# LED.net
KiCad netlist of a schematic drawn in Altium Designer
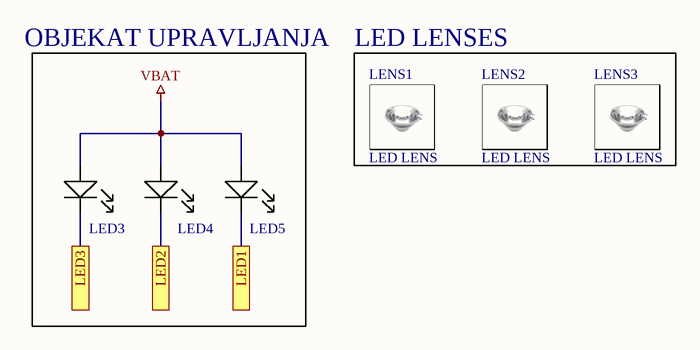
[diagram p0: LED.SchDoc]

(export (version "E")
  (design (tool "Eeschema 10.0.6"))
  (components
    (comp (ref "LED3")
      (value "JB2835BWT-N-U65EA0000-N000P001")
      (footprint "LED_1411")
      (description "LED Lighting J White, Cool 6500K 3-Step MacAdam Ellipse 2.7V 55mA 120° 1411 (3528 Metric)")
      (libsource (lib "Library-AutomatskoOsvetljenje") (part "LED COOL WHITE"))
    )
    (comp (ref "LED4")
      (value "JB2835BWT-N-U65EA0000-N000P001")
      (footprint "LED_1411")
      (description "LED Lighting J White, Cool 6500K 3-Step MacAdam Ellipse 2.7V 55mA 120° 1411 (3528 Metric)")
      (libsource (lib "Library-AutomatskoOsvetljenje") (part "LED COOL WHITE"))
    )
    (comp (ref "LED5")
      (value "JB2835BWT-N-U65EA0000-N000P001")
      (footprint "LED_1411")
      (description "LED Lighting J White, Cool 6500K 3-Step MacAdam Ellipse 2.7V 55mA 120° 1411 (3528 Metric)")
      (libsource (lib "Library-AutomatskoOsvetljenje") (part "LED COOL WHITE"))
    )
    (comp (ref "LENS1")
      (value "LED LENS")
      (description "LENS CLR 15-33DEG MEDIUM SNAP-IN")
      (fields (field (name "MPN") "10003/15"))
      (libsource (lib "Library-AutomatskoOsvetljenje") (part "LED LENS"))
    )
    (comp (ref "LENS2")
      (value "LED LENS")
      (description "LENS CLR 15-33DEG MEDIUM SNAP-IN")
      (fields (field (name "MPN") "10003/15"))
      (libsource (lib "Library-AutomatskoOsvetljenje") (part "LED LENS"))
    )
    (comp (ref "LENS3")
      (value "LED LENS")
      (description "LENS CLR 15-33DEG MEDIUM SNAP-IN")
      (fields (field (name "MPN") "10003/15"))
      (libsource (lib "Library-AutomatskoOsvetljenje") (part "LED LENS"))
    )
  )
  (nets
    (net (code "1") (name "/LED1") (class "Default")
      (node (ref "LED5") (pin "2") (pinfunction "Cathode_2") (pintype "passive"))
    )
    (net (code "2") (name "/LED2") (class "Default")
      (node (ref "LED4") (pin "2") (pinfunction "Cathode_2") (pintype "passive"))
    )
    (net (code "3") (name "/LED3") (class "Default")
      (node (ref "LED3") (pin "2") (pinfunction "Cathode_2") (pintype "passive"))
    )
    (net (code "4") (name "VBAT") (class "Default")
      (node (ref "LED3") (pin "1") (pinfunction "Anode_1") (pintype "passive"))
      (node (ref "LED4") (pin "1") (pinfunction "Anode_1") (pintype "passive"))
      (node (ref "LED5") (pin "1") (pinfunction "Anode_1") (pintype "passive"))
    )
  )
)
